# SOTB_LWC.net
KiCad netlist of a schematic drawn in EAGLE
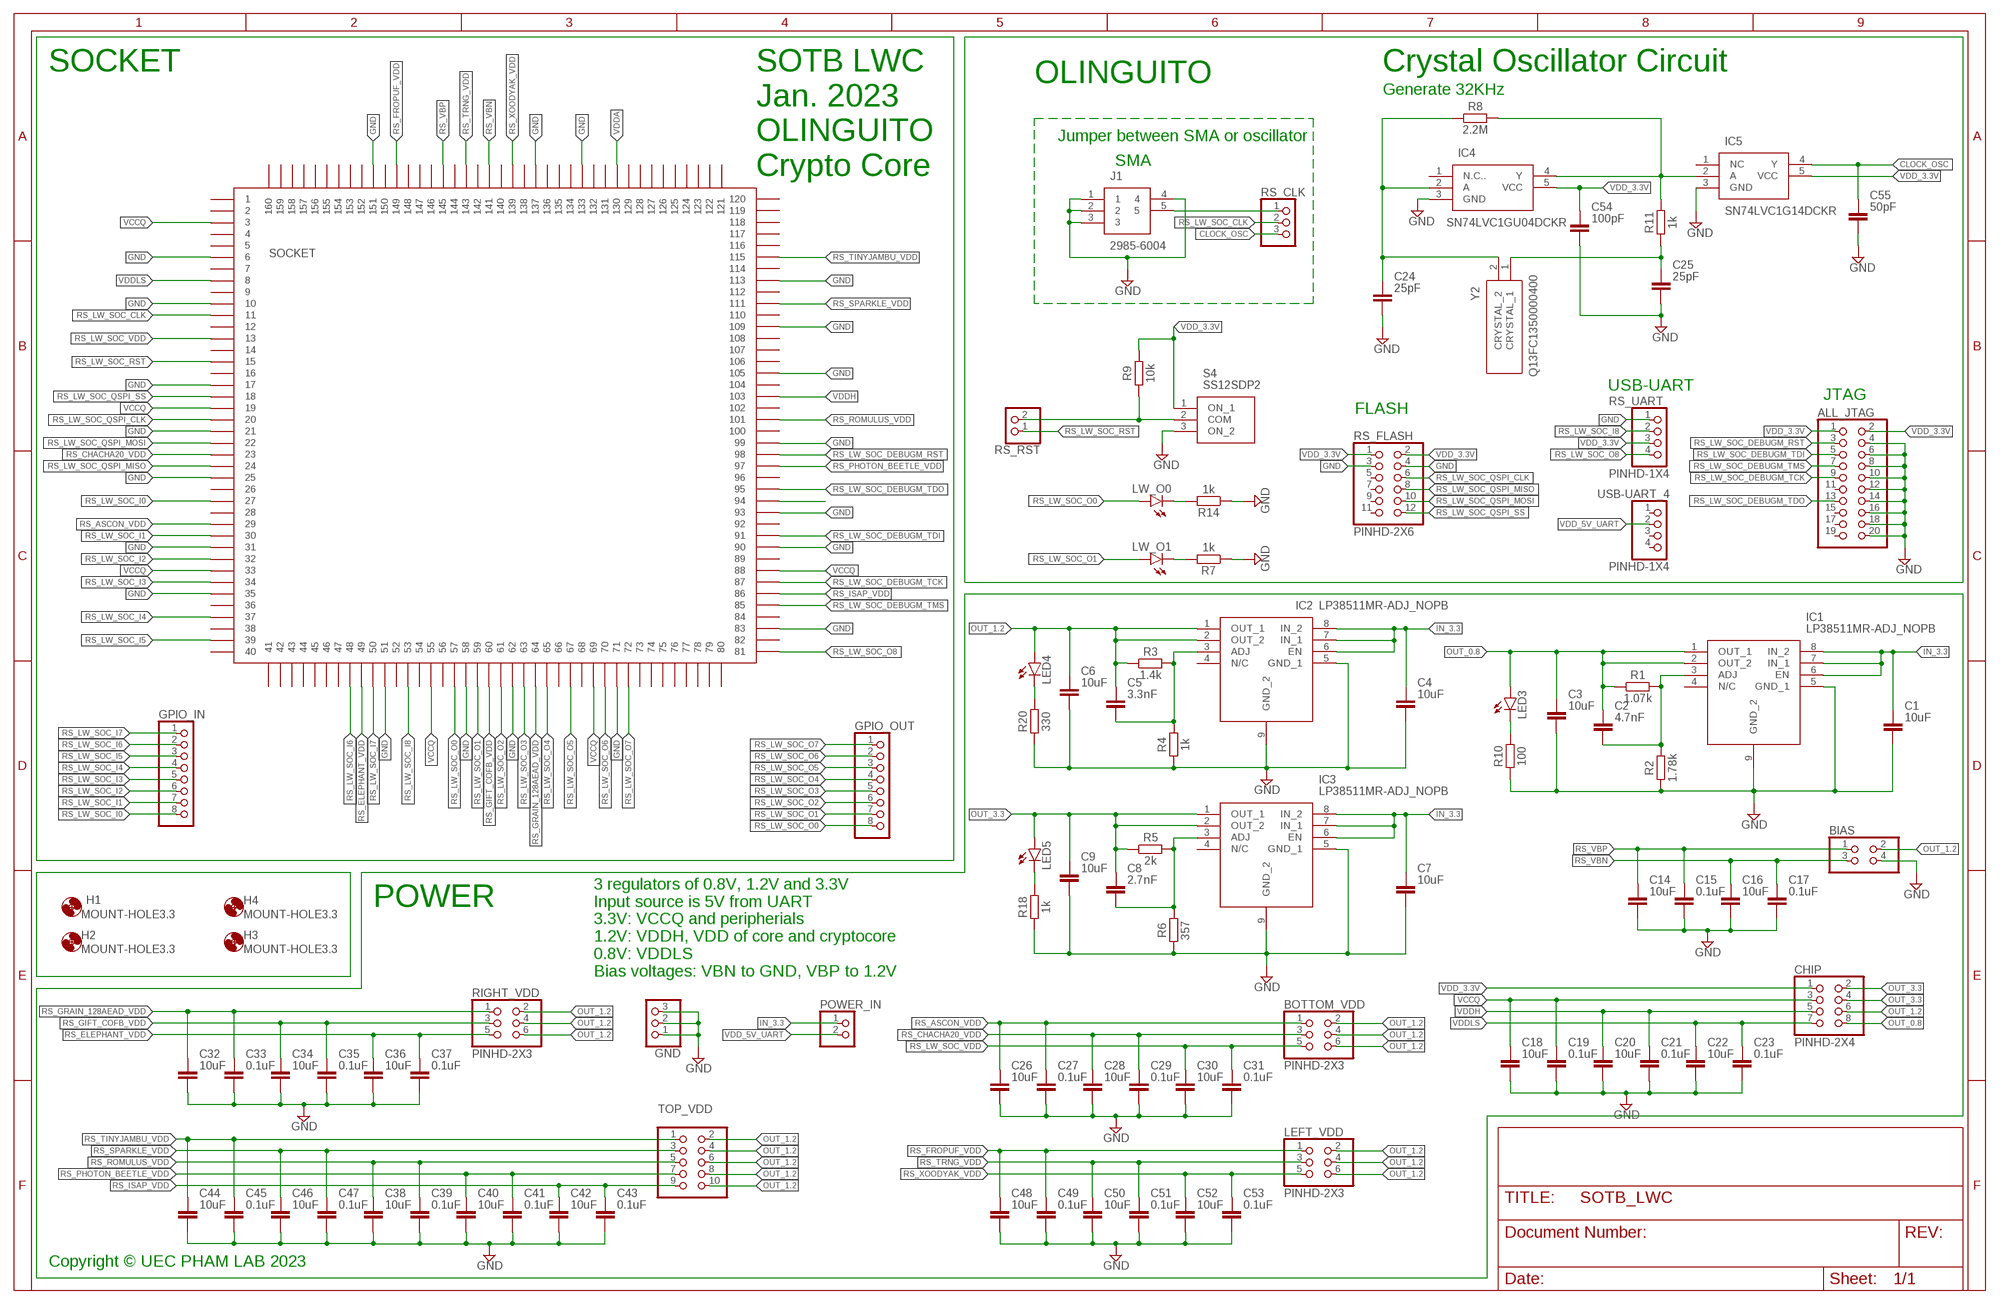
[diagram p0: schematic, sheet 1]

(export (version "E")
  (design (tool "Eeschema 10.0.6"))
  (components
    (comp (ref "ALL_JTAG")
      (value "PINHD-2X10")
      (footprint "eagle-import:2X10")
      (libsource (lib "eagle-import") (part "PINHD-2X10"))
    )
    (comp (ref "BIAS")
      (value "PINHD-2X2")
      (footprint "eagle-import:2X02")
      (libsource (lib "eagle-import") (part "PINHD-2X2"))
    )
    (comp (ref "BOTTOM_VDD")
      (value "PINHD-2X3")
      (footprint "eagle-import:2X03")
      (libsource (lib "eagle-import") (part "PINHD-2X3"))
    )
    (comp (ref "C1")
      (value "10uF")
      (footprint "eagle-import:CAPC3216X135")
      (libsource (lib "eagle-import") (part "CCHIP-1206(3216-METRIC)_"))
    )
    (comp (ref "C2")
      (value "4.7nF")
      (footprint "eagle-import:CAPC3216X135")
      (libsource (lib "eagle-import") (part "CCHIP-1206(3216-METRIC)_"))
    )
    (comp (ref "C3")
      (value "10uF")
      (footprint "eagle-import:CAPC3216X135")
      (libsource (lib "eagle-import") (part "CCHIP-1206(3216-METRIC)_"))
    )
    (comp (ref "C4")
      (value "10uF")
      (footprint "eagle-import:CAPC3216X135")
      (libsource (lib "eagle-import") (part "CCHIP-1206(3216-METRIC)_"))
    )
    (comp (ref "C5")
      (value "3.3nF")
      (footprint "eagle-import:CAPC3216X135")
      (libsource (lib "eagle-import") (part "CCHIP-1206(3216-METRIC)_"))
    )
    (comp (ref "C6")
      (value "10uF")
      (footprint "eagle-import:CAPC3216X135")
      (libsource (lib "eagle-import") (part "CCHIP-1206(3216-METRIC)_"))
    )
    (comp (ref "C7")
      (value "10uF")
      (footprint "eagle-import:CAPC3216X135")
      (libsource (lib "eagle-import") (part "CCHIP-1206(3216-METRIC)_"))
    )
    (comp (ref "C8")
      (value "2.7nF")
      (footprint "eagle-import:CAPC3216X135")
      (libsource (lib "eagle-import") (part "CCHIP-1206(3216-METRIC)_"))
    )
    (comp (ref "C9")
      (value "10uF")
      (footprint "eagle-import:CAPC3216X135")
      (libsource (lib "eagle-import") (part "CCHIP-1206(3216-METRIC)_"))
    )
    (comp (ref "C14")
      (value "10uF")
      (footprint "eagle-import:CAPC3216X135")
      (libsource (lib "eagle-import") (part "CCHIP-1206(3216-METRIC)_"))
    )
    (comp (ref "C15")
      (value "0.1uF")
      (footprint "eagle-import:CAPC3216X135")
      (libsource (lib "eagle-import") (part "CCHIP-1206(3216-METRIC)_"))
    )
    (comp (ref "C16")
      (value "10uF")
      (footprint "eagle-import:CAPC3216X135")
      (libsource (lib "eagle-import") (part "CCHIP-1206(3216-METRIC)_"))
    )
    (comp (ref "C17")
      (value "0.1uF")
      (footprint "eagle-import:CAPC3216X135")
      (libsource (lib "eagle-import") (part "CCHIP-1206(3216-METRIC)_"))
    )
    (comp (ref "C18")
      (value "10uF")
      (footprint "eagle-import:CAPC3216X135")
      (libsource (lib "eagle-import") (part "CCHIP-1206(3216-METRIC)_"))
    )
    (comp (ref "C19")
      (value "0.1uF")
      (footprint "eagle-import:CAPC3216X135")
      (libsource (lib "eagle-import") (part "CCHIP-1206(3216-METRIC)_"))
    )
    (comp (ref "C20")
      (value "10uF")
      (footprint "eagle-import:CAPC3216X135")
      (libsource (lib "eagle-import") (part "CCHIP-1206(3216-METRIC)_"))
    )
    (comp (ref "C21")
      (value "0.1uF")
      (footprint "eagle-import:CAPC3216X135")
      (libsource (lib "eagle-import") (part "CCHIP-1206(3216-METRIC)_"))
    )
    (comp (ref "C22")
      (value "10uF")
      (footprint "eagle-import:CAPC3216X135")
      (libsource (lib "eagle-import") (part "CCHIP-1206(3216-METRIC)_"))
    )
    (comp (ref "C23")
      (value "0.1uF")
      (footprint "eagle-import:CAPC3216X135")
      (libsource (lib "eagle-import") (part "CCHIP-1206(3216-METRIC)_"))
    )
    (comp (ref "C24")
      (value "25pF")
      (footprint "eagle-import:CAPC2012X110")
      (libsource (lib "eagle-import") (part "CCHIP-0805(2012-METRIC)_"))
    )
    (comp (ref "C25")
      (value "25pF")
      (footprint "eagle-import:CAPC2012X110")
      (libsource (lib "eagle-import") (part "CCHIP-0805(2012-METRIC)_"))
    )
    (comp (ref "C26")
      (value "10uF")
      (footprint "eagle-import:CAPC3216X135")
      (libsource (lib "eagle-import") (part "CCHIP-1206(3216-METRIC)_"))
    )
    (comp (ref "C27")
      (value "0.1uF")
      (footprint "eagle-import:CAPC3216X135")
      (libsource (lib "eagle-import") (part "CCHIP-1206(3216-METRIC)_"))
    )
    (comp (ref "C28")
      (value "10uF")
      (footprint "eagle-import:CAPC3216X135")
      (libsource (lib "eagle-import") (part "CCHIP-1206(3216-METRIC)_"))
    )
    (comp (ref "C29")
      (value "0.1uF")
      (footprint "eagle-import:CAPC3216X135")
      (libsource (lib "eagle-import") (part "CCHIP-1206(3216-METRIC)_"))
    )
    (comp (ref "C30")
      (value "10uF")
      (footprint "eagle-import:CAPC3216X135")
      (libsource (lib "eagle-import") (part "CCHIP-1206(3216-METRIC)_"))
    )
    (comp (ref "C31")
      (value "0.1uF")
      (footprint "eagle-import:CAPC3216X135")
      (libsource (lib "eagle-import") (part "CCHIP-1206(3216-METRIC)_"))
    )
    (comp (ref "C32")
      (value "10uF")
      (footprint "eagle-import:CAPC3216X135")
      (libsource (lib "eagle-import") (part "CCHIP-1206(3216-METRIC)_"))
    )
    (comp (ref "C33")
      (value "0.1uF")
      (footprint "eagle-import:CAPC3216X135")
      (libsource (lib "eagle-import") (part "CCHIP-1206(3216-METRIC)_"))
    )
    (comp (ref "C34")
      (value "10uF")
      (footprint "eagle-import:CAPC3216X135")
      (libsource (lib "eagle-import") (part "CCHIP-1206(3216-METRIC)_"))
    )
    (comp (ref "C35")
      (value "0.1uF")
      (footprint "eagle-import:CAPC3216X135")
      (libsource (lib "eagle-import") (part "CCHIP-1206(3216-METRIC)_"))
    )
    (comp (ref "C36")
      (value "10uF")
      (footprint "eagle-import:CAPC3216X135")
      (libsource (lib "eagle-import") (part "CCHIP-1206(3216-METRIC)_"))
    )
    (comp (ref "C37")
      (value "0.1uF")
      (footprint "eagle-import:CAPC3216X135")
      (libsource (lib "eagle-import") (part "CCHIP-1206(3216-METRIC)_"))
    )
    (comp (ref "C38")
      (value "10uF")
      (footprint "eagle-import:CAPC3216X135")
      (libsource (lib "eagle-import") (part "CCHIP-1206(3216-METRIC)_"))
    )
    (comp (ref "C39")
      (value "0.1uF")
      (footprint "eagle-import:CAPC3216X135")
      (libsource (lib "eagle-import") (part "CCHIP-1206(3216-METRIC)_"))
    )
    (comp (ref "C40")
      (value "10uF")
      (footprint "eagle-import:CAPC3216X135")
      (libsource (lib "eagle-import") (part "CCHIP-1206(3216-METRIC)_"))
    )
    (comp (ref "C41")
      (value "0.1uF")
      (footprint "eagle-import:CAPC3216X135")
      (libsource (lib "eagle-import") (part "CCHIP-1206(3216-METRIC)_"))
    )
    (comp (ref "C42")
      (value "10uF")
      (footprint "eagle-import:CAPC3216X135")
      (libsource (lib "eagle-import") (part "CCHIP-1206(3216-METRIC)_"))
    )
    (comp (ref "C43")
      (value "0.1uF")
      (footprint "eagle-import:CAPC3216X135")
      (libsource (lib "eagle-import") (part "CCHIP-1206(3216-METRIC)_"))
    )
    (comp (ref "C44")
      (value "10uF")
      (footprint "eagle-import:CAPC3216X135")
      (libsource (lib "eagle-import") (part "CCHIP-1206(3216-METRIC)_"))
    )
    (comp (ref "C45")
      (value "0.1uF")
      (footprint "eagle-import:CAPC3216X135")
      (libsource (lib "eagle-import") (part "CCHIP-1206(3216-METRIC)_"))
    )
    (comp (ref "C46")
      (value "10uF")
      (footprint "eagle-import:CAPC3216X135")
      (libsource (lib "eagle-import") (part "CCHIP-1206(3216-METRIC)_"))
    )
    (comp (ref "C47")
      (value "0.1uF")
      (footprint "eagle-import:CAPC3216X135")
      (libsource (lib "eagle-import") (part "CCHIP-1206(3216-METRIC)_"))
    )
    (comp (ref "C48")
      (value "10uF")
      (footprint "eagle-import:CAPC3216X135")
      (libsource (lib "eagle-import") (part "CCHIP-1206(3216-METRIC)_"))
    )
    (comp (ref "C49")
      (value "0.1uF")
      (footprint "eagle-import:CAPC3216X135")
      (libsource (lib "eagle-import") (part "CCHIP-1206(3216-METRIC)_"))
    )
    (comp (ref "C50")
      (value "10uF")
      (footprint "eagle-import:CAPC3216X135")
      (libsource (lib "eagle-import") (part "CCHIP-1206(3216-METRIC)_"))
    )
    (comp (ref "C51")
      (value "0.1uF")
      (footprint "eagle-import:CAPC3216X135")
      (libsource (lib "eagle-import") (part "CCHIP-1206(3216-METRIC)_"))
    )
    (comp (ref "C52")
      (value "10uF")
      (footprint "eagle-import:CAPC3216X135")
      (libsource (lib "eagle-import") (part "CCHIP-1206(3216-METRIC)_"))
    )
    (comp (ref "C53")
      (value "0.1uF")
      (footprint "eagle-import:CAPC3216X135")
      (libsource (lib "eagle-import") (part "CCHIP-1206(3216-METRIC)_"))
    )
    (comp (ref "C54")
      (value "100pF")
      (footprint "eagle-import:CAPC2012X110")
      (libsource (lib "eagle-import") (part "CCHIP-0805(2012-METRIC)_"))
    )
    (comp (ref "C55")
      (value "50pF")
      (footprint "eagle-import:CAPC2012X110")
      (libsource (lib "eagle-import") (part "CCHIP-0805(2012-METRIC)_"))
    )
    (comp (ref "CHIP")
      (value "PINHD-2X4")
      (footprint "eagle-import:2X04")
      (libsource (lib "eagle-import") (part "PINHD-2X4"))
    )
    (comp (ref "GND")
      (value "PINHD-1X3")
      (footprint "eagle-import:1X03")
      (libsource (lib "eagle-import") (part "PINHD-1X3"))
    )
    (comp (ref "GPIO_IN")
      (value "PINHD-1X8")
      (footprint "eagle-import:1X08")
      (libsource (lib "eagle-import") (part "PINHD-1X8"))
    )
    (comp (ref "GPIO_OUT")
      (value "PINHD-1X8")
      (footprint "eagle-import:1X08")
      (libsource (lib "eagle-import") (part "PINHD-1X8"))
    )
    (comp (ref "H1")
      (value "MOUNT-HOLE3.3")
      (footprint "eagle-import:3,3")
      (libsource (lib "eagle-import") (part "MOUNT-HOLE3.3"))
    )
    (comp (ref "H2")
      (value "MOUNT-HOLE3.3")
      (footprint "eagle-import:3,3")
      (libsource (lib "eagle-import") (part "MOUNT-HOLE3.3"))
    )
    (comp (ref "H3")
      (value "MOUNT-HOLE3.3")
      (footprint "eagle-import:3,3")
      (libsource (lib "eagle-import") (part "MOUNT-HOLE3.3"))
    )
    (comp (ref "H4")
      (value "MOUNT-HOLE3.3")
      (footprint "eagle-import:3,3")
      (libsource (lib "eagle-import") (part "MOUNT-HOLE3.3"))
    )
    (comp (ref "IC1")
      (value "LP38511MR-ADJ_NOPB")
      (footprint "eagle-import:SOIC127P600X170-9N")
      (fields
        (field (name "ARROW_PART_NUMBER") "LP38511MR-ADJ/NOPB")
        (field (name "MOUSER_PART_NUMBER") "926-38511MR-ADJ/NOPB")
      )
      (libsource (lib "eagle-import") (part "LP38511MR-ADJ_NOPB"))
    )
    (comp (ref "IC2")
      (value "LP38511MR-ADJ_NOPB")
      (footprint "eagle-import:SOIC127P600X170-9N")
      (fields
        (field (name "ARROW_PART_NUMBER") "LP38511MR-ADJ/NOPB")
        (field (name "MOUSER_PART_NUMBER") "926-38511MR-ADJ/NOPB")
      )
      (libsource (lib "eagle-import") (part "LP38511MR-ADJ_NOPB"))
    )
    (comp (ref "IC3")
      (value "LP38511MR-ADJ_NOPB")
      (footprint "eagle-import:SOIC127P600X170-9N")
      (fields
        (field (name "ARROW_PART_NUMBER") "LP38511MR-ADJ/NOPB")
        (field (name "MOUSER_PART_NUMBER") "926-38511MR-ADJ/NOPB")
      )
      (libsource (lib "eagle-import") (part "LP38511MR-ADJ_NOPB"))
    )
    (comp (ref "IC4")
      (value "SN74LVC1GU04DCKR")
      (footprint "eagle-import:SOT65P210X110-5N")
      (fields (field (name "MOUSER_PART_NUMBER") "595-SN74LVC1GU04DCKR"))
      (libsource (lib "eagle-import") (part "SN74LVC1GU04DCKR"))
    )
    (comp (ref "IC5")
      (value "SN74LVC1G14DCKR")
      (footprint "eagle-import:SOT65P210X110-5N")
      (fields (field (name "MOUSER_PART_NUMBER") "595-SN74LVC1G14DCKR"))
      (libsource (lib "eagle-import") (part "SN74LVC1G14DCKR"))
    )
    (comp (ref "J1")
      (value "2985-6004")
      (footprint "eagle-import:29856004")
      (fields (field (name "MOUSER_PART_NUMBER") "523-2985-6004"))
      (libsource (lib "eagle-import") (part "2985-6004"))
    )
    (comp (ref "LED3")
      (value "LEDCHIPLED_0805")
      (footprint "eagle-import:CHIPLED_0805")
      (libsource (lib "eagle-import") (part "LEDCHIPLED_0805"))
    )
    (comp (ref "LED4")
      (value "LEDCHIPLED_0805")
      (footprint "eagle-import:CHIPLED_0805")
      (libsource (lib "eagle-import") (part "LEDCHIPLED_0805"))
    )
    (comp (ref "LED5")
      (value "LEDCHIPLED_0805")
      (footprint "eagle-import:CHIPLED_0805")
      (libsource (lib "eagle-import") (part "LEDCHIPLED_0805"))
    )
    (comp (ref "LEFT_VDD")
      (value "PINHD-2X3")
      (footprint "eagle-import:2X03")
      (libsource (lib "eagle-import") (part "PINHD-2X3"))
    )
    (comp (ref "LW_O0")
      (value "LEDCHIPLED_0805")
      (footprint "eagle-import:CHIPLED_0805")
      (libsource (lib "eagle-import") (part "LEDCHIPLED_0805"))
    )
    (comp (ref "LW_O1")
      (value "LEDCHIPLED_0805")
      (footprint "eagle-import:CHIPLED_0805")
      (libsource (lib "eagle-import") (part "LEDCHIPLED_0805"))
    )
    (comp (ref "POWER_IN")
      (value "PINHD-1X2")
      (footprint "eagle-import:1X02")
      (libsource (lib "eagle-import") (part "PINHD-1X2"))
    )
    (comp (ref "R1")
      (value "1.07k")
      (footprint "eagle-import:RESC3216X70")
      (libsource (lib "eagle-import") (part "RCHIP-1206(3216-METRIC)_"))
    )
    (comp (ref "R2")
      (value "1.78k")
      (footprint "eagle-import:RESC3216X70")
      (libsource (lib "eagle-import") (part "RCHIP-1206(3216-METRIC)_"))
    )
    (comp (ref "R3")
      (value "1.4k")
      (footprint "eagle-import:RESC3216X70")
      (libsource (lib "eagle-import") (part "RCHIP-1206(3216-METRIC)_"))
    )
    (comp (ref "R4")
      (value "1k")
      (footprint "eagle-import:RESC3216X70")
      (libsource (lib "eagle-import") (part "RCHIP-1206(3216-METRIC)_"))
    )
    (comp (ref "R5")
      (value "2k")
      (footprint "eagle-import:RESC3216X70")
      (libsource (lib "eagle-import") (part "RCHIP-1206(3216-METRIC)_"))
    )
    (comp (ref "R6")
      (value "357")
      (footprint "eagle-import:RESC3216X70")
      (libsource (lib "eagle-import") (part "RCHIP-1206(3216-METRIC)_"))
    )
    (comp (ref "R7")
      (value "1k")
      (footprint "eagle-import:RESC3216X70")
      (libsource (lib "eagle-import") (part "RCHIP-1206(3216-METRIC)_"))
    )
    (comp (ref "R8")
      (value "2.2M")
      (footprint "eagle-import:RESC3216X70")
      (libsource (lib "eagle-import") (part "RCHIP-1206(3216-METRIC)_"))
    )
    (comp (ref "R9")
      (value "10k")
      (footprint "eagle-import:RESC3216X70")
      (libsource (lib "eagle-import") (part "RCHIP-1206(3216-METRIC)_"))
    )
    (comp (ref "R10")
      (value "100")
      (footprint "eagle-import:RESC3216X70")
      (libsource (lib "eagle-import") (part "RCHIP-1206(3216-METRIC)_"))
    )
    (comp (ref "R11")
      (value "1k")
      (footprint "eagle-import:RESC3216X70")
      (libsource (lib "eagle-import") (part "RCHIP-1206(3216-METRIC)_"))
    )
    (comp (ref "R14")
      (value "1k")
      (footprint "eagle-import:RESC3216X70")
      (libsource (lib "eagle-import") (part "RCHIP-1206(3216-METRIC)_"))
    )
    (comp (ref "R18")
      (value "1k")
      (footprint "eagle-import:RESC3216X70")
      (libsource (lib "eagle-import") (part "RCHIP-1206(3216-METRIC)_"))
    )
    (comp (ref "R20")
      (value "330")
      (footprint "eagle-import:RESC3216X70")
      (libsource (lib "eagle-import") (part "RCHIP-1206(3216-METRIC)_"))
    )
    (comp (ref "RIGHT_VDD")
      (value "PINHD-2X3")
      (footprint "eagle-import:2X03")
      (libsource (lib "eagle-import") (part "PINHD-2X3"))
    )
    (comp (ref "RS_CLK")
      (value "PINHD-1X3")
      (footprint "eagle-import:1X03")
      (libsource (lib "eagle-import") (part "PINHD-1X3"))
    )
    (comp (ref "RS_FLASH")
      (value "PINHD-2X6")
      (footprint "eagle-import:2X06")
      (libsource (lib "eagle-import") (part "PINHD-2X6"))
    )
    (comp (ref "RS_RST")
      (value "PINHD-1X2")
      (footprint "eagle-import:1X02")
      (libsource (lib "eagle-import") (part "PINHD-1X2"))
    )
    (comp (ref "RS_UART")
      (value "PINHD-1X4")
      (footprint "eagle-import:1X04")
      (libsource (lib "eagle-import") (part "PINHD-1X4"))
    )
    (comp (ref "S4")
      (value "SS12SDP2")
      (footprint "eagle-import:SS12SDP2")
      (fields (field (name "MOUSER_PART_NUMBER") "633-SS12SDP2"))
      (libsource (lib "eagle-import") (part "SS12SDP2"))
    )
    (comp (ref "SOCKET")
      (value "QFP28-160PIN")
      (footprint "eagle-import:QFP28-160PIN")
      (libsource (lib "eagle-import") (part "QFP28-160PIN"))
    )
    (comp (ref "TOP_VDD")
      (value "PINHD-2X5")
      (footprint "eagle-import:2X05")
      (libsource (lib "eagle-import") (part "PINHD-2X5"))
    )
    (comp (ref "USB-UART_4")
      (value "PINHD-1X4")
      (footprint "eagle-import:1X04")
      (libsource (lib "eagle-import") (part "PINHD-1X4"))
    )
    (comp (ref "Y2")
      (value "Q13FC1350000400")
      (footprint "eagle-import:Q13FC1350000400")
      (libsource (lib "eagle-import") (part "Q13FC1350000400"))
    )
  )
  (nets
    (net (code "1") (name "CLOCK_OSC") (class "Default")
      (node (ref "C55") (pin "1") (pinfunction "1_1") (pintype "passive"))
      (node (ref "IC5") (pin "4") (pinfunction "Y_4") (pintype "bidirectional"))
      (node (ref "RS_CLK") (pin "3") (pinfunction "3_3") (pintype "passive"))
    )
    (net (code "2") (name "GND") (class "Default")
      (node (ref "ALL_JTAG") (pin "10") (pinfunction "10_10") (pintype "passive"))
      (node (ref "ALL_JTAG") (pin "12") (pinfunction "12_12") (pintype "passive"))
      (node (ref "ALL_JTAG") (pin "14") (pinfunction "14_14") (pintype "passive"))
      (node (ref "ALL_JTAG") (pin "16") (pinfunction "16_16") (pintype "passive"))
      (node (ref "ALL_JTAG") (pin "18") (pinfunction "18_18") (pintype "passive"))
      (node (ref "ALL_JTAG") (pin "20") (pinfunction "20_20") (pintype "passive"))
      (node (ref "ALL_JTAG") (pin "4") (pinfunction "4_4") (pintype "passive"))
      (node (ref "ALL_JTAG") (pin "6") (pinfunction "6_6") (pintype "passive"))
      (node (ref "ALL_JTAG") (pin "8") (pinfunction "8_8") (pintype "passive"))
      (node (ref "BIAS") (pin "4") (pinfunction "4_4") (pintype "passive"))
      (node (ref "C1") (pin "2") (pinfunction "2_2") (pintype "passive"))
      (node (ref "C14") (pin "2") (pinfunction "2_2") (pintype "passive"))
      (node (ref "C15") (pin "2") (pinfunction "2_2") (pintype "passive"))
      (node (ref "C16") (pin "2") (pinfunction "2_2") (pintype "passive"))
      (node (ref "C17") (pin "2") (pinfunction "2_2") (pintype "passive"))
      (node (ref "C18") (pin "2") (pinfunction "2_2") (pintype "passive"))
      (node (ref "C19") (pin "2") (pinfunction "2_2") (pintype "passive"))
      (node (ref "C20") (pin "2") (pinfunction "2_2") (pintype "passive"))
      (node (ref "C21") (pin "2") (pinfunction "2_2") (pintype "passive"))
      (node (ref "C22") (pin "2") (pinfunction "2_2") (pintype "passive"))
      (node (ref "C23") (pin "2") (pinfunction "2_2") (pintype "passive"))
      (node (ref "C24") (pin "2") (pinfunction "2_2") (pintype "passive"))
      (node (ref "C25") (pin "2") (pinfunction "2_2") (pintype "passive"))
      (node (ref "C26") (pin "2") (pinfunction "2_2") (pintype "passive"))
      (node (ref "C27") (pin "2") (pinfunction "2_2") (pintype "passive"))
      (node (ref "C28") (pin "2") (pinfunction "2_2") (pintype "passive"))
      (node (ref "C29") (pin "2") (pinfunction "2_2") (pintype "passive"))
      (node (ref "C3") (pin "2") (pinfunction "2_2") (pintype "passive"))
      (node (ref "C30") (pin "2") (pinfunction "2_2") (pintype "passive"))
      (node (ref "C31") (pin "2") (pinfunction "2_2") (pintype "passive"))
      (node (ref "C32") (pin "2") (pinfunction "2_2") (pintype "passive"))
      (node (ref "C33") (pin "2") (pinfunction "2_2") (pintype "passive"))
      (node (ref "C34") (pin "2") (pinfunction "2_2") (pintype "passive"))
      (node (ref "C35") (pin "2") (pinfunction "2_2") (pintype "passive"))
      (node (ref "C36") (pin "2") (pinfunction "2_2") (pintype "passive"))
      (node (ref "C37") (pin "2") (pinfunction "2_2") (pintype "passive"))
      (node (ref "C38") (pin "2") (pinfunction "2_2") (pintype "passive"))
      (node (ref "C39") (pin "2") (pinfunction "2_2") (pintype "passive"))
      (node (ref "C4") (pin "2") (pinfunction "2_2") (pintype "passive"))
      (node (ref "C40") (pin "2") (pinfunction "2_2") (pintype "passive"))
      (node (ref "C41") (pin "2") (pinfunction "2_2") (pintype "passive"))
      (node (ref "C42") (pin "2") (pinfunction "2_2") (pintype "passive"))
      (node (ref "C43") (pin "2") (pinfunction "2_2") (pintype "passive"))
      (node (ref "C44") (pin "2") (pinfunction "2_2") (pintype "passive"))
      (node (ref "C45") (pin "2") (pinfunction "2_2") (pintype "passive"))
      (node (ref "C46") (pin "2") (pinfunction "2_2") (pintype "passive"))
      (node (ref "C47") (pin "2") (pinfunction "2_2") (pintype "passive"))
      (node (ref "C48") (pin "2") (pinfunction "2_2") (pintype "passive"))
      (node (ref "C49") (pin "2") (pinfunction "2_2") (pintype "passive"))
      (node (ref "C50") (pin "2") (pinfunction "2_2") (pintype "passive"))
      (node (ref "C51") (pin "2") (pinfunction "2_2") (pintype "passive"))
      (node (ref "C52") (pin "2") (pinfunction "2_2") (pintype "passive"))
      (node (ref "C53") (pin "2") (pinfunction "2_2") (pintype "passive"))
      (node (ref "C54") (pin "2") (pinfunction "2_2") (pintype "passive"))
      (node (ref "C55") (pin "2") (pinfunction "2_2") (pintype "passive"))
      (node (ref "C6") (pin "2") (pinfunction "2_2") (pintype "passive"))
      (node (ref "C7") (pin "2") (pinfunction "2_2") (pintype "passive"))
      (node (ref "C9") (pin "2") (pinfunction "2_2") (pintype "passive"))
      (node (ref "GND") (pin "1") (pinfunction "1_1") (pintype "passive"))
      (node (ref "GND") (pin "2") (pinfunction "2_2") (pintype "passive"))
      (node (ref "GND") (pin "3") (pinfunction "3_3") (pintype "passive"))
      (node (ref "IC1") (pin "5") (pinfunction "GND_1_5") (pintype "bidirectional"))
      (node (ref "IC1") (pin "9") (pinfunction "GND_2_9") (pintype "bidirectional"))
      (node (ref "IC2") (pin "5") (pinfunction "GND_1_5") (pintype "bidirectional"))
      (node (ref "IC2") (pin "9") (pinfunction "GND_2_9") (pintype "bidirectional"))
      (node (ref "IC3") (pin "5") (pinfunction "GND_1_5") (pintype "bidirectional"))
      (node (ref "IC3") (pin "9") (pinfunction "GND_2_9") (pintype "bidirectional"))
      (node (ref "IC4") (pin "3") (pinfunction "GND_3") (pintype "bidirectional"))
      (node (ref "IC5") (pin "3") (pinfunction "GND_3") (pintype "power_in"))
      (node (ref "J1") (pin "1") (pinfunction "1_1") (pintype "bidirectional"))
      (node (ref "J1") (pin "2") (pinfunction "2_2") (pintype "bidirectional"))
      (node (ref "J1") (pin "3") (pinfunction "3_3") (pintype "bidirectional"))
      (node (ref "J1") (pin "4") (pinfunction "4_4") (pintype "bidirectional"))
      (node (ref "R10") (pin "1") (pinfunction "1_1") (pintype "passive"))
      (node (ref "R14") (pin "1") (pinfunction "1_1") (pintype "passive"))
      (node (ref "R18") (pin "1") (pinfunction "1_1") (pintype "passive"))
      (node (ref "R2") (pin "1") (pinfunction "1_1") (pintype "passive"))
      (node (ref "R20") (pin "1") (pinfunction "1_1") (pintype "passive"))
      (node (ref "R4") (pin "1") (pinfunction "1_1") (pintype "passive"))
      (node (ref "R6") (pin "1") (pinfunction "1_1") (pintype "passive"))
      (node (ref "R7") (pin "1") (pinfunction "1_1") (pintype "passive"))
      (node (ref "RS_FLASH") (pin "3") (pinfunction "3_3") (pintype "passive"))
      (node (ref "RS_FLASH") (pin "4") (pinfunction "4_4") (pintype "passive"))
      (node (ref "RS_UART") (pin "1") (pinfunction "1_1") (pintype "passive"))
      (node (ref "S4") (pin "3") (pinfunction "ON_2_3") (pintype "bidirectional"))
      (node (ref "SOCKET") (pin "P$10") (pinfunction "10_P$10") (pintype "bidirectional"))
      (node (ref "SOCKET") (pin "P$105") (pinfunction "105_P$105") (pintype "bidirectional"))
      (node (ref "SOCKET") (pin "P$109") (pinfunction "109_P$109") (pintype "bidirectional"))
      (node (ref "SOCKET") (pin "P$113") (pinfunction "113_P$113") (pintype "bidirectional"))
      (node (ref "SOCKET") (pin "P$133") (pinfunction "133_P$133") (pintype "bidirectional"))
      (node (ref "SOCKET") (pin "P$137") (pinfunction "137_P$137") (pintype "bidirectional"))
      (node (ref "SOCKET") (pin "P$151") (pinfunction "151_P$151") (pintype "bidirectional"))
      (node (ref "SOCKET") (pin "P$17") (pinfunction "17_P$17") (pintype "bidirectional"))
      (node (ref "SOCKET") (pin "P$21") (pinfunction "21_P$21") (pintype "bidirectional"))
      (node (ref "SOCKET") (pin "P$25") (pinfunction "25_P$25") (pintype "bidirectional"))
      (node (ref "SOCKET") (pin "P$31") (pinfunction "31_P$31") (pintype "bidirectional"))
      (node (ref "SOCKET") (pin "P$35") (pinfunction "35_P$35") (pintype "bidirectional"))
      (node (ref "SOCKET") (pin "P$51") (pinfunction "51_P$51") (pintype "bidirectional"))
      (node (ref "SOCKET") (pin "P$58") (pinfunction "58_P$58") (pintype "bidirectional"))
      (node (ref "SOCKET") (pin "P$6") (pinfunction "6_P$6") (pintype "bidirectional"))
      (node (ref "SOCKET") (pin "P$62") (pinfunction "62_P$62") (pintype "bidirectional"))
      (node (ref "SOCKET") (pin "P$71") (pinfunction "71_P$71") (pintype "bidirectional"))
      (node (ref "SOCKET") (pin "P$83") (pinfunction "83_P$83") (pintype "bidirectional"))
      (node (ref "SOCKET") (pin "P$90") (pinfunction "90_P$90") (pintype "bidirectional"))
      (node (ref "SOCKET") (pin "P$93") (pinfunction "93_P$93") (pintype "bidirectional"))
      (node (ref "SOCKET") (pin "P$99") (pinfunction "99_P$99") (pintype "bidirectional"))
    )
    (net (code "3") (name "IN_3.3") (class "Default")
      (node (ref "C1") (pin "1") (pinfunction "1_1") (pintype "passive"))
      (node (ref "C4") (pin "1") (pinfunction "1_1") (pintype "passive"))
      (node (ref "C7") (pin "1") (pinfunction "1_1") (pintype "passive"))
      (node (ref "IC1") (pin "6") (pinfunction "EN_6") (pintype "bidirectional"))
      (node (ref "IC1") (pin "7") (pinfunction "IN_1_7") (pintype "bidirectional"))
      (node (ref "IC1") (pin "8") (pinfunction "IN_2_8") (pintype "bidirectional"))
      (node (ref "IC2") (pin "6") (pinfunction "EN_6") (pintype "bidirectional"))
      (node (ref "IC2") (pin "7") (pinfunction "IN_1_7") (pintype "bidirectional"))
      (node (ref "IC2") (pin "8") (pinfunction "IN_2_8") (pintype "bidirectional"))
      (node (ref "IC3") (pin "6") (pinfunction "EN_6") (pintype "bidirectional"))
      (node (ref "IC3") (pin "7") (pinfunction "IN_1_7") (pintype "bidirectional"))
      (node (ref "IC3") (pin "8") (pinfunction "IN_2_8") (pintype "bidirectional"))
      (node (ref "POWER_IN") (pin "1") (pinfunction "1_1") (pintype "passive"))
    )
    (net (code "4") (name "Net-(IC1-ADJ)") (class "Default")
      (node (ref "C2") (pin "2") (pinfunction "2_2") (pintype "passive"))
      (node (ref "IC1") (pin "3") (pinfunction "ADJ_3") (pintype "bidirectional"))
      (node (ref "R1") (pin "2") (pinfunction "2_2") (pintype "passive"))
      (node (ref "R2") (pin "2") (pinfunction "2_2") (pintype "passive"))
    )
    (net (code "5") (name "Net-(IC2-ADJ)") (class "Default")
      (node (ref "C5") (pin "2") (pinfunction "2_2") (pintype "passive"))
      (node (ref "IC2") (pin "3") (pinfunction "ADJ_3") (pintype "bidirectional"))
      (node (ref "R3") (pin "2") (pinfunction "2_2") (pintype "passive"))
      (node (ref "R4") (pin "2") (pinfunction "2_2") (pintype "passive"))
    )
    (net (code "6") (name "Net-(IC3-ADJ)") (class "Default")
      (node (ref "C8") (pin "2") (pinfunction "2_2") (pintype "passive"))
      (node (ref "IC3") (pin "3") (pinfunction "ADJ_3") (pintype "bidirectional"))
      (node (ref "R5") (pin "2") (pinfunction "2_2") (pintype "passive"))
      (node (ref "R6") (pin "2") (pinfunction "2_2") (pintype "passive"))
    )
    (net (code "7") (name "Net-(IC4-A)") (class "Default")
      (node (ref "C24") (pin "1") (pinfunction "1_1") (pintype "passive"))
      (node (ref "IC4") (pin "2") (pinfunction "A_2") (pintype "bidirectional"))
      (node (ref "R8") (pin "1") (pinfunction "1_1") (pintype "passive"))
      (node (ref "Y2") (pin "2") (pinfunction "CRYSTAL_2_2") (pintype "bidirectional"))
    )
    (net (code "8") (name "Net-(IC4-Y)") (class "Default")
      (node (ref "IC4") (pin "4") (pinfunction "Y_4") (pintype "bidirectional"))
      (node (ref "IC5") (pin "2") (pinfunction "A_2") (pintype "bidirectional"))
      (node (ref "R11") (pin "2") (pinfunction "2_2") (pintype "passive"))
      (node (ref "R8") (pin "2") (pinfunction "2_2") (pintype "passive"))
    )
    (net (code "9") (name "Net-(J1-Pad5)") (class "Default")
      (node (ref "J1") (pin "5") (pinfunction "5_5") (pintype "bidirectional"))
      (node (ref "RS_CLK") (pin "1") (pinfunction "1_1") (pintype "passive"))
    )
    (net (code "10") (name "Net-(LED3-PadC)") (class "Default")
      (node (ref "LED3") (pin "C") (pinfunction "C_C") (pintype "passive"))
      (node (ref "R10") (pin "2") (pinfunction "2_2") (pintype "passive"))
    )
    (net (code "11") (name "Net-(LED4-PadC)") (class "Default")
      (node (ref "LED4") (pin "C") (pinfunction "C_C") (pintype "passive"))
      (node (ref "R20") (pin "2") (pinfunction "2_2") (pintype "passive"))
    )
    (net (code "12") (name "Net-(LED5-PadC)") (class "Default")
      (node (ref "LED5") (pin "C") (pinfunction "C_C") (pintype "passive"))
      (node (ref "R18") (pin "2") (pinfunction "2_2") (pintype "passive"))
    )
    (net (code "13") (name "Net-(LW_O0-PadC)") (class "Default")
      (node (ref "LW_O0") (pin "C") (pinfunction "C_C") (pintype "passive"))
      (node (ref "R14") (pin "2") (pinfunction "2_2") (pintype "passive"))
    )
    (net (code "14") (name "Net-(LW_O1-PadC)") (class "Default")
      (node (ref "LW_O1") (pin "C") (pinfunction "C_C") (pintype "passive"))
      (node (ref "R7") (pin "2") (pinfunction "2_2") (pintype "passive"))
    )
    (net (code "15") (name "Net-(S4-COM)") (class "Default")
      (node (ref "R9") (pin "1") (pinfunction "1_1") (pintype "passive"))
      (node (ref "RS_RST") (pin "2") (pinfunction "2_2") (pintype "passive"))
      (node (ref "S4") (pin "2") (pinfunction "COM_2") (pintype "bidirectional"))
    )
    (net (code "16") (name "Net-(Y2-CRYSTAL_1)") (class "Default")
      (node (ref "C25") (pin "1") (pinfunction "1_1") (pintype "passive"))
      (node (ref "R11") (pin "1") (pinfunction "1_1") (pintype "passive"))
      (node (ref "Y2") (pin "1") (pinfunction "CRYSTAL_1_1") (pintype "bidirectional"))
    )
    (net (code "17") (name "OUT_0.8") (class "Default")
      (node (ref "C2") (pin "1") (pinfunction "1_1") (pintype "passive"))
      (node (ref "C3") (pin "1") (pinfunction "1_1") (pintype "passive"))
      (node (ref "CHIP") (pin "8") (pinfunction "8_8") (pintype "passive"))
      (node (ref "IC1") (pin "1") (pinfunction "OUT_1_1") (pintype "bidirectional"))
      (node (ref "IC1") (pin "2") (pinfunction "OUT_2_2") (pintype "bidirectional"))
      (node (ref "LED3") (pin "A") (pinfunction "A_A") (pintype "passive"))
      (node (ref "R1") (pin "1") (pinfunction "1_1") (pintype "passive"))
    )
    (net (code "18") (name "OUT_1.2") (class "Default")
      (node (ref "BIAS") (pin "2") (pinfunction "2_2") (pintype "passive"))
      (node (ref "BOTTOM_VDD") (pin "2") (pinfunction "2_2") (pintype "passive"))
      (node (ref "BOTTOM_VDD") (pin "4") (pinfunction "4_4") (pintype "passive"))
      (node (ref "BOTTOM_VDD") (pin "6") (pinfunction "6_6") (pintype "passive"))
      (node (ref "C5") (pin "1") (pinfunction "1_1") (pintype "passive"))
      (node (ref "C6") (pin "1") (pinfunction "1_1") (pintype "passive"))
      (node (ref "CHIP") (pin "6") (pinfunction "6_6") (pintype "passive"))
      (node (ref "IC2") (pin "1") (pinfunction "OUT_1_1") (pintype "bidirectional"))
      (node (ref "IC2") (pin "2") (pinfunction "OUT_2_2") (pintype "bidirectional"))
      (node (ref "LED4") (pin "A") (pinfunction "A_A") (pintype "passive"))
      (node (ref "LEFT_VDD") (pin "2") (pinfunction "2_2") (pintype "passive"))
      (node (ref "LEFT_VDD") (pin "4") (pinfunction "4_4") (pintype "passive"))
      (node (ref "LEFT_VDD") (pin "6") (pinfunction "6_6") (pintype "passive"))
      (node (ref "R3") (pin "1") (pinfunction "1_1") (pintype "passive"))
      (node (ref "RIGHT_VDD") (pin "2") (pinfunction "2_2") (pintype "passive"))
      (node (ref "RIGHT_VDD") (pin "4") (pinfunction "4_4") (pintype "passive"))
      (node (ref "RIGHT_VDD") (pin "6") (pinfunction "6_6") (pintype "passive"))
      (node (ref "TOP_VDD") (pin "10") (pinfunction "10_10") (pintype "passive"))
      (node (ref "TOP_VDD") (pin "2") (pinfunction "2_2") (pintype "passive"))
      (node (ref "TOP_VDD") (pin "4") (pinfunction "4_4") (pintype "passive"))
      (node (ref "TOP_VDD") (pin "6") (pinfunction "6_6") (pintype "passive"))
      (node (ref "TOP_VDD") (pin "8") (pinfunction "8_8") (pintype "passive"))
    )
    (net (code "19") (name "OUT_3.3") (class "Default")
      (node (ref "C8") (pin "1") (pinfunction "1_1") (pintype "passive"))
      (node (ref "C9") (pin "1") (pinfunction "1_1") (pintype "passive"))
      (node (ref "CHIP") (pin "2") (pinfunction "2_2") (pintype "passive"))
      (node (ref "CHIP") (pin "4") (pinfunction "4_4") (pintype "passive"))
      (node (ref "IC3") (pin "1") (pinfunction "OUT_1_1") (pintype "bidirectional"))
      (node (ref "IC3") (pin "2") (pinfunction "OUT_2_2") (pintype "bidirectional"))
      (node (ref "LED5") (pin "A") (pinfunction "A_A") (pintype "passive"))
      (node (ref "R5") (pin "1") (pinfunction "1_1") (pintype "passive"))
    )
    (net (code "20") (name "RS_ASCON_VDD") (class "Default")
      (node (ref "BOTTOM_VDD") (pin "1") (pinfunction "1_1") (pintype "passive"))
      (node (ref "C26") (pin "1") (pinfunction "1_1") (pintype "passive"))
      (node (ref "C27") (pin "1") (pinfunction "1_1") (pintype "passive"))
      (node (ref "SOCKET") (pin "P$29") (pinfunction "29_P$29") (pintype "bidirectional"))
    )
    (net (code "21") (name "RS_CHACHA20_VDD") (class "Default")
      (node (ref "BOTTOM_VDD") (pin "3") (pinfunction "3_3") (pintype "passive"))
      (node (ref "C28") (pin "1") (pinfunction "1_1") (pintype "passive"))
      (node (ref "C29") (pin "1") (pinfunction "1_1") (pintype "passive"))
      (node (ref "SOCKET") (pin "P$23") (pinfunction "23_P$23") (pintype "bidirectional"))
    )
    (net (code "22") (name "RS_ELEPHANT_VDD") (class "Default")
      (node (ref "C36") (pin "1") (pinfunction "1_1") (pintype "passive"))
      (node (ref "C37") (pin "1") (pinfunction "1_1") (pintype "passive"))
      (node (ref "RIGHT_VDD") (pin "5") (pinfunction "5_5") (pintype "passive"))
      (node (ref "SOCKET") (pin "P$49") (pinfunction "49_P$49") (pintype "bidirectional"))
    )
    (net (code "23") (name "RS_FROPUF_VDD") (class "Default")
      (node (ref "C48") (pin "1") (pinfunction "1_1") (pintype "passive"))
      (node (ref "C49") (pin "1") (pinfunction "1_1") (pintype "passive"))
      (node (ref "LEFT_VDD") (pin "1") (pinfunction "1_1") (pintype "passive"))
      (node (ref "SOCKET") (pin "P$149") (pinfunction "149_P$149") (pintype "bidirectional"))
    )
    (net (code "24") (name "RS_GIFT_COFB_VDD") (class "Default")
      (node (ref "C34") (pin "1") (pinfunction "1_1") (pintype "passive"))
      (node (ref "C35") (pin "1") (pinfunction "1_1") (pintype "passive"))
      (node (ref "RIGHT_VDD") (pin "3") (pinfunction "3_3") (pintype "passive"))
      (node (ref "SOCKET") (pin "P$60") (pinfunction "60_P$60") (pintype "bidirectional"))
    )
    (net (code "25") (name "RS_GRAIN_128AEAD_VDD") (class "Default")
      (node (ref "C32") (pin "1") (pinfunction "1_1") (pintype "passive"))
      (node (ref "C33") (pin "1") (pinfunction "1_1") (pintype "passive"))
      (node (ref "RIGHT_VDD") (pin "1") (pinfunction "1_1") (pintype "passive"))
      (node (ref "SOCKET") (pin "P$64") (pinfunction "64_P$64") (pintype "bidirectional"))
    )
    (net (code "26") (name "RS_ISAP_VDD") (class "Default")
      (node (ref "C42") (pin "1") (pinfunction "1_1") (pintype "passive"))
      (node (ref "C43") (pin "1") (pinfunction "1_1") (pintype "passive"))
      (node (ref "SOCKET") (pin "P$86") (pinfunction "86_P$86") (pintype "bidirectional"))
      (node (ref "TOP_VDD") (pin "9") (pinfunction "9_9") (pintype "passive"))
    )
    (net (code "27") (name "RS_LW_SOC_CLK") (class "Default")
      (node (ref "RS_CLK") (pin "2") (pinfunction "2_2") (pintype "passive"))
      (node (ref "SOCKET") (pin "P$11") (pinfunction "11_P$11") (pintype "bidirectional"))
    )
    (net (code "28") (name "RS_LW_SOC_DEBUGM_RST") (class "Default")
      (node (ref "ALL_JTAG") (pin "3") (pinfunction "3_3") (pintype "passive"))
      (node (ref "SOCKET") (pin "P$98") (pinfunction "98_P$98") (pintype "bidirectional"))
    )
    (net (code "29") (name "RS_LW_SOC_DEBUGM_TCK") (class "Default")
      (node (ref "ALL_JTAG") (pin "9") (pinfunction "9_9") (pintype "passive"))
      (node (ref "SOCKET") (pin "P$87") (pinfunction "87_P$87") (pintype "bidirectional"))
    )
    (net (code "30") (name "RS_LW_SOC_DEBUGM_TDI") (class "Default")
      (node (ref "ALL_JTAG") (pin "5") (pinfunction "5_5") (pintype "passive"))
      (node (ref "SOCKET") (pin "P$91") (pinfunction "91_P$91") (pintype "bidirectional"))
    )
    (net (code "31") (name "RS_LW_SOC_DEBUGM_TDO") (class "Default")
      (node (ref "ALL_JTAG") (pin "13") (pinfunction "13_13") (pintype "passive"))
      (node (ref "SOCKET") (pin "P$95") (pinfunction "95_P$95") (pintype "bidirectional"))
    )
    (net (code "32") (name "RS_LW_SOC_DEBUGM_TMS") (class "Default")
      (node (ref "ALL_JTAG") (pin "7") (pinfunction "7_7") (pintype "passive"))
      (node (ref "SOCKET") (pin "P$85") (pinfunction "85_P$85") (pintype "bidirectional"))
    )
    (net (code "33") (name "RS_LW_SOC_I0") (class "Default")
      (node (ref "GPIO_IN") (pin "8") (pinfunction "8_8") (pintype "passive"))
      (node (ref "SOCKET") (pin "P$27") (pinfunction "27_P$27") (pintype "bidirectional"))
    )
    (net (code "34") (name "RS_LW_SOC_I1") (class "Default")
      (node (ref "GPIO_IN") (pin "7") (pinfunction "7_7") (pintype "passive"))
      (node (ref "SOCKET") (pin "P$30") (pinfunction "30_P$30") (pintype "bidirectional"))
    )
    (net (code "35") (name "RS_LW_SOC_I2") (class "Default")
      (node (ref "GPIO_IN") (pin "6") (pinfunction "6_6") (pintype "passive"))
      (node (ref "SOCKET") (pin "P$32") (pinfunction "32_P$32") (pintype "bidirectional"))
    )
    (net (code "36") (name "RS_LW_SOC_I3") (class "Default")
      (node (ref "GPIO_IN") (pin "5") (pinfunction "5_5") (pintype "passive"))
      (node (ref "SOCKET") (pin "P$34") (pinfunction "34_P$34") (pintype "bidirectional"))
    )
    (net (code "37") (name "RS_LW_SOC_I4") (class "Default")
      (node (ref "GPIO_IN") (pin "4") (pinfunction "4_4") (pintype "passive"))
      (node (ref "SOCKET") (pin "P$37") (pinfunction "37_P$37") (pintype "bidirectional"))
    )
    (net (code "38") (name "RS_LW_SOC_I5") (class "Default")
      (node (ref "GPIO_IN") (pin "3") (pinfunction "3_3") (pintype "passive"))
      (node (ref "SOCKET") (pin "P$39") (pinfunction "39_P$39") (pintype "bidirectional"))
    )
    (net (code "39") (name "RS_LW_SOC_I6") (class "Default")
      (node (ref "GPIO_IN") (pin "2") (pinfunction "2_2") (pintype "passive"))
      (node (ref "SOCKET") (pin "P$48") (pinfunction "48_P$48") (pintype "bidirectional"))
    )
    (net (code "40") (name "RS_LW_SOC_I7") (class "Default")
      (node (ref "GPIO_IN") (pin "1") (pinfunction "1_1") (pintype "passive"))
      (node (ref "SOCKET") (pin "P$50") (pinfunction "50_P$50") (pintype "bidirectional"))
    )
    (net (code "41") (name "RS_LW_SOC_I8") (class "Default")
      (node (ref "RS_UART") (pin "2") (pinfunction "2_2") (pintype "passive"))
      (node (ref "SOCKET") (pin "P$53") (pinfunction "53_P$53") (pintype "bidirectional"))
    )
    (net (code "42") (name "RS_LW_SOC_O0") (class "Default")
      (node (ref "GPIO_OUT") (pin "8") (pinfunction "8_8") (pintype "passive"))
      (node (ref "LW_O0") (pin "A") (pinfunction "A_A") (pintype "passive"))
      (node (ref "SOCKET") (pin "P$57") (pinfunction "57_P$57") (pintype "bidirectional"))
    )
    (net (code "43") (name "RS_LW_SOC_O1") (class "Default")
      (node (ref "GPIO_OUT") (pin "7") (pinfunction "7_7") (pintype "passive"))
      (node (ref "LW_O1") (pin "A") (pinfunction "A_A") (pintype "passive"))
      (node (ref "SOCKET") (pin "P$59") (pinfunction "59_P$59") (pintype "bidirectional"))
    )
    (net (code "44") (name "RS_LW_SOC_O2") (class "Default")
      (node (ref "GPIO_OUT") (pin "6") (pinfunction "6_6") (pintype "passive"))
      (node (ref "SOCKET") (pin "P$61") (pinfunction "61_P$61") (pintype "bidirectional"))
    )
    (net (code "45") (name "RS_LW_SOC_O3") (class "Default")
      (node (ref "GPIO_OUT") (pin "5") (pinfunction "5_5") (pintype "passive"))
      (node (ref "SOCKET") (pin "P$63") (pinfunction "63_P$63") (pintype "bidirectional"))
    )
    (net (code "46") (name "RS_LW_SOC_O4") (class "Default")
      (node (ref "GPIO_OUT") (pin "4") (pinfunction "4_4") (pintype "passive"))
      (node (ref "SOCKET") (pin "P$65") (pinfunction "65_P$65") (pintype "bidirectional"))
    )
    (net (code "47") (name "RS_LW_SOC_O5") (class "Default")
      (node (ref "GPIO_OUT") (pin "3") (pinfunction "3_3") (pintype "passive"))
      (node (ref "SOCKET") (pin "P$67") (pinfunction "67_P$67") (pintype "bidirectional"))
    )
    (net (code "48") (name "RS_LW_SOC_O6") (class "Default")
      (node (ref "GPIO_OUT") (pin "2") (pinfunction "2_2") (pintype "passive"))
      (node (ref "SOCKET") (pin "P$70") (pinfunction "70_P$70") (pintype "bidirectional"))
    )
    (net (code "49") (name "RS_LW_SOC_O7") (class "Default")
      (node (ref "GPIO_OUT") (pin "1") (pinfunction "1_1") (pintype "passive"))
      (node (ref "SOCKET") (pin "P$72") (pinfunction "72_P$72") (pintype "bidirectional"))
    )
    (net (code "50") (name "RS_LW_SOC_O8") (class "Default")
      (node (ref "RS_UART") (pin "4") (pinfunction "4_4") (pintype "passive"))
      (node (ref "SOCKET") (pin "P$81") (pinfunction "81_P$81") (pintype "bidirectional"))
    )
    (net (code "51") (name "RS_LW_SOC_QSPI_CLK") (class "Default")
      (node (ref "RS_FLASH") (pin "6") (pinfunction "6_6") (pintype "passive"))
      (node (ref "SOCKET") (pin "P$20") (pinfunction "20_P$20") (pintype "bidirectional"))
    )
    (net (code "52") (name "RS_LW_SOC_QSPI_MISO") (class "Default")
      (node (ref "RS_FLASH") (pin "8") (pinfunction "8_8") (pintype "passive"))
      (node (ref "SOCKET") (pin "P$24") (pinfunction "24_P$24") (pintype "bidirectional"))
    )
    (net (code "53") (name "RS_LW_SOC_QSPI_MOSI") (class "Default")
      (node (ref "RS_FLASH") (pin "10") (pinfunction "10_10") (pintype "passive"))
      (node (ref "SOCKET") (pin "P$22") (pinfunction "22_P$22") (pintype "bidirectional"))
    )
    (net (code "54") (name "RS_LW_SOC_QSPI_SS") (class "Default")
      (node (ref "RS_FLASH") (pin "12") (pinfunction "12_12") (pintype "passive"))
      (node (ref "SOCKET") (pin "P$18") (pinfunction "18_P$18") (pintype "bidirectional"))
    )
    (net (code "55") (name "RS_LW_SOC_RST") (class "Default")
      (node (ref "RS_RST") (pin "1") (pinfunction "1_1") (pintype "passive"))
      (node (ref "SOCKET") (pin "P$15") (pinfunction "15_P$15") (pintype "bidirectional"))
    )
    (net (code "56") (name "RS_LW_SOC_VDD") (class "Default")
      (node (ref "BOTTOM_VDD") (pin "5") (pinfunction "5_5") (pintype "passive"))
      (node (ref "C30") (pin "1") (pinfunction "1_1") (pintype "passive"))
      (node (ref "C31") (pin "1") (pinfunction "1_1") (pintype "passive"))
      (node (ref "SOCKET") (pin "P$13") (pinfunction "13_P$13") (pintype "bidirectional"))
    )
    (net (code "57") (name "RS_PHOTON_BEETLE_VDD") (class "Default")
      (node (ref "C40") (pin "1") (pinfunction "1_1") (pintype "passive"))
      (node (ref "C41") (pin "1") (pinfunction "1_1") (pintype "passive"))
      (node (ref "SOCKET") (pin "P$97") (pinfunction "97_P$97") (pintype "bidirectional"))
      (node (ref "TOP_VDD") (pin "7") (pinfunction "7_7") (pintype "passive"))
    )
    (net (code "58") (name "RS_ROMULUS_VDD") (class "Default")
      (node (ref "C38") (pin "1") (pinfunction "1_1") (pintype "passive"))
      (node (ref "C39") (pin "1") (pinfunction "1_1") (pintype "passive"))
      (node (ref "SOCKET") (pin "P$101") (pinfunction "101_P$101") (pintype "bidirectional"))
      (node (ref "TOP_VDD") (pin "5") (pinfunction "5_5") (pintype "passive"))
    )
    (net (code "59") (name "RS_SPARKLE_VDD") (class "Default")
      (node (ref "C46") (pin "1") (pinfunction "1_1") (pintype "passive"))
      (node (ref "C47") (pin "1") (pinfunction "1_1") (pintype "passive"))
      (node (ref "SOCKET") (pin "P$111") (pinfunction "111_P$111") (pintype "bidirectional"))
      (node (ref "TOP_VDD") (pin "3") (pinfunction "3_3") (pintype "passive"))
    )
    (net (code "60") (name "RS_TINYJAMBU_VDD") (class "Default")
      (node (ref "C44") (pin "1") (pinfunction "1_1") (pintype "passive"))
      (node (ref "C45") (pin "1") (pinfunction "1_1") (pintype "passive"))
      (node (ref "SOCKET") (pin "P$115") (pinfunction "115_P$115") (pintype "bidirectional"))
      (node (ref "TOP_VDD") (pin "1") (pinfunction "1_1") (pintype "passive"))
    )
    (net (code "61") (name "RS_TRNG_VDD") (class "Default")
      (node (ref "C50") (pin "1") (pinfunction "1_1") (pintype "passive"))
      (node (ref "C51") (pin "1") (pinfunction "1_1") (pintype "passive"))
      (node (ref "LEFT_VDD") (pin "3") (pinfunction "3_3") (pintype "passive"))
      (node (ref "SOCKET") (pin "P$143") (pinfunction "143_P$143") (pintype "bidirectional"))
    )
    (net (code "62") (name "RS_VBN") (class "Default")
      (node (ref "BIAS") (pin "3") (pinfunction "3_3") (pintype "passive"))
      (node (ref "C16") (pin "1") (pinfunction "1_1") (pintype "passive"))
      (node (ref "C17") (pin "1") (pinfunction "1_1") (pintype "passive"))
      (node (ref "SOCKET") (pin "P$141") (pinfunction "141_P$141") (pintype "bidirectional"))
    )
    (net (code "63") (name "RS_VBP") (class "Default")
      (node (ref "BIAS") (pin "1") (pinfunction "1_1") (pintype "passive"))
      (node (ref "C14") (pin "1") (pinfunction "1_1") (pintype "passive"))
      (node (ref "C15") (pin "1") (pinfunction "1_1") (pintype "passive"))
      (node (ref "SOCKET") (pin "P$145") (pinfunction "145_P$145") (pintype "bidirectional"))
    )
    (net (code "64") (name "RS_XOODYAK_VDD") (class "Default")
      (node (ref "C52") (pin "1") (pinfunction "1_1") (pintype "passive"))
      (node (ref "C53") (pin "1") (pinfunction "1_1") (pintype "passive"))
      (node (ref "LEFT_VDD") (pin "5") (pinfunction "5_5") (pintype "passive"))
      (node (ref "SOCKET") (pin "P$139") (pinfunction "139_P$139") (pintype "bidirectional"))
    )
    (net (code "65") (name "VCCQ") (class "Default")
      (node (ref "C18") (pin "1") (pinfunction "1_1") (pintype "passive"))
      (node (ref "C19") (pin "1") (pinfunction "1_1") (pintype "passive"))
      (node (ref "CHIP") (pin "3") (pinfunction "3_3") (pintype "passive"))
      (node (ref "SOCKET") (pin "P$19") (pinfunction "19_P$19") (pintype "bidirectional"))
      (node (ref "SOCKET") (pin "P$3") (pinfunction "3_P$3") (pintype "bidirectional"))
      (node (ref "SOCKET") (pin "P$33") (pinfunction "33_P$33") (pintype "bidirectional"))
      (node (ref "SOCKET") (pin "P$55") (pinfunction "55_P$55") (pintype "bidirectional"))
      (node (ref "SOCKET") (pin "P$69") (pinfunction "69_P$69") (pintype "bidirectional"))
      (node (ref "SOCKET") (pin "P$88") (pinfunction "88_P$88") (pintype "bidirectional"))
    )
    (net (code "66") (name "VDDA") (class "Default")
      (node (ref "SOCKET") (pin "P$130") (pinfunction "130_P$130") (pintype "bidirectional"))
    )
    (net (code "67") (name "VDDH") (class "Default")
      (node (ref "C20") (pin "1") (pinfunction "1_1") (pintype "passive"))
      (node (ref "C21") (pin "1") (pinfunction "1_1") (pintype "passive"))
      (node (ref "CHIP") (pin "5") (pinfunction "5_5") (pintype "passive"))
      (node (ref "SOCKET") (pin "P$103") (pinfunction "103_P$103") (pintype "bidirectional"))
    )
    (net (code "68") (name "VDDLS") (class "Default")
      (node (ref "C22") (pin "1") (pinfunction "1_1") (pintype "passive"))
      (node (ref "C23") (pin "1") (pinfunction "1_1") (pintype "passive"))
      (node (ref "CHIP") (pin "7") (pinfunction "7_7") (pintype "passive"))
      (node (ref "SOCKET") (pin "P$8") (pinfunction "8_P$8") (pintype "bidirectional"))
    )
    (net (code "69") (name "VDD_3.3V") (class "Default")
      (node (ref "ALL_JTAG") (pin "1") (pinfunction "1_1") (pintype "passive"))
      (node (ref "ALL_JTAG") (pin "2") (pinfunction "2_2") (pintype "passive"))
      (node (ref "C54") (pin "1") (pinfunction "1_1") (pintype "passive"))
      (node (ref "CHIP") (pin "1") (pinfunction "1_1") (pintype "passive"))
      (node (ref "IC4") (pin "5") (pinfunction "VCC_5") (pintype "bidirectional"))
      (node (ref "IC5") (pin "5") (pinfunction "VCC_5") (pintype "power_in"))
      (node (ref "R9") (pin "2") (pinfunction "2_2") (pintype "passive"))
      (node (ref "RS_FLASH") (pin "1") (pinfunction "1_1") (pintype "passive"))
      (node (ref "RS_FLASH") (pin "2") (pinfunction "2_2") (pintype "passive"))
      (node (ref "RS_UART") (pin "3") (pinfunction "3_3") (pintype "passive"))
      (node (ref "S4") (pin "1") (pinfunction "ON_1_1") (pintype "bidirectional"))
    )
    (net (code "70") (name "VDD_5V_UART") (class "Default")
      (node (ref "POWER_IN") (pin "2") (pinfunction "2_2") (pintype "passive"))
      (node (ref "USB-UART_4") (pin "2") (pinfunction "2_2") (pintype "passive"))
    )
    (net (code "71") (name "unconnected-(ALL_JTAG-Pad11)") (class "Default")
      (node (ref "ALL_JTAG") (pin "11") (pinfunction "11_11") (pintype "passive"))
    )
    (net (code "72") (name "unconnected-(ALL_JTAG-Pad15)") (class "Default")
      (node (ref "ALL_JTAG") (pin "15") (pinfunction "15_15") (pintype "passive"))
    )
    (net (code "73") (name "unconnected-(ALL_JTAG-Pad17)") (class "Default")
      (node (ref "ALL_JTAG") (pin "17") (pinfunction "17_17") (pintype "passive"))
    )
    (net (code "74") (name "unconnected-(ALL_JTAG-Pad19)") (class "Default")
      (node (ref "ALL_JTAG") (pin "19") (pinfunction "19_19") (pintype "passive"))
    )
    (net (code "75") (name "unconnected-(IC1-N{slash}C-Pad4)") (class "Default")
      (node (ref "IC1") (pin "4") (pinfunction "N/C_4") (pintype "no_connect"))
    )
    (net (code "76") (name "unconnected-(IC2-N{slash}C-Pad4)") (class "Default")
      (node (ref "IC2") (pin "4") (pinfunction "N/C_4") (pintype "no_connect"))
    )
    (net (code "77") (name "unconnected-(IC3-N{slash}C-Pad4)") (class "Default")
      (node (ref "IC3") (pin "4") (pinfunction "N/C_4") (pintype "no_connect"))
    )
    (net (code "78") (name "unconnected-(IC4-N.C..-Pad1)") (class "Default")
      (node (ref "IC4") (pin "1") (pinfunction "N.C.._1") (pintype "bidirectional"))
    )
    (net (code "79") (name "unconnected-(IC5-NC-Pad1)") (class "Default")
      (node (ref "IC5") (pin "1") (pinfunction "NC_1") (pintype "no_connect"))
    )
    (net (code "80") (name "unconnected-(RS_FLASH-Pad5)") (class "Default")
      (node (ref "RS_FLASH") (pin "5") (pinfunction "5_5") (pintype "passive"))
    )
    (net (code "81") (name "unconnected-(RS_FLASH-Pad7)") (class "Default")
      (node (ref "RS_FLASH") (pin "7") (pinfunction "7_7") (pintype "passive"))
    )
    (net (code "82") (name "unconnected-(RS_FLASH-Pad9)") (class "Default")
      (node (ref "RS_FLASH") (pin "9") (pinfunction "9_9") (pintype "passive"))
    )
    (net (code "83") (name "unconnected-(RS_FLASH-Pad11)") (class "Default")
      (node (ref "RS_FLASH") (pin "11") (pinfunction "11_11") (pintype "passive"))
    )
    (net (code "84") (name "unconnected-(SOCKET-1-PadP$1)") (class "Default")
      (node (ref "SOCKET") (pin "P$1") (pinfunction "1_P$1") (pintype "bidirectional"))
    )
    (net (code "85") (name "unconnected-(SOCKET-2-PadP$2)") (class "Default")
      (node (ref "SOCKET") (pin "P$2") (pinfunction "2_P$2") (pintype "bidirectional"))
    )
    (net (code "86") (name "unconnected-(SOCKET-4-PadP$4)") (class "Default")
      (node (ref "SOCKET") (pin "P$4") (pinfunction "4_P$4") (pintype "bidirectional"))
    )
    (net (code "87") (name "unconnected-(SOCKET-5-PadP$5)") (class "Default")
      (node (ref "SOCKET") (pin "P$5") (pinfunction "5_P$5") (pintype "bidirectional"))
    )
    (net (code "88") (name "unconnected-(SOCKET-7-PadP$7)") (class "Default")
      (node (ref "SOCKET") (pin "P$7") (pinfunction "7_P$7") (pintype "bidirectional"))
    )
    (net (code "89") (name "unconnected-(SOCKET-9-PadP$9)") (class "Default")
      (node (ref "SOCKET") (pin "P$9") (pinfunction "9_P$9") (pintype "bidirectional"))
    )
    (net (code "90") (name "unconnected-(SOCKET-12-PadP$12)") (class "Default")
      (node (ref "SOCKET") (pin "P$12") (pinfunction "12_P$12") (pintype "bidirectional"))
    )
    (net (code "91") (name "unconnected-(SOCKET-14-PadP$14)") (class "Default")
      (node (ref "SOCKET") (pin "P$14") (pinfunction "14_P$14") (pintype "bidirectional"))
    )
    (net (code "92") (name "unconnected-(SOCKET-16-PadP$16)") (class "Default")
      (node (ref "SOCKET") (pin "P$16") (pinfunction "16_P$16") (pintype "bidirectional"))
    )
    (net (code "93") (name "unconnected-(SOCKET-26-PadP$26)") (class "Default")
      (node (ref "SOCKET") (pin "P$26") (pinfunction "26_P$26") (pintype "bidirectional"))
    )
    (net (code "94") (name "unconnected-(SOCKET-28-PadP$28)") (class "Default")
      (node (ref "SOCKET") (pin "P$28") (pinfunction "28_P$28") (pintype "bidirectional"))
    )
    (net (code "95") (name "unconnected-(SOCKET-36-PadP$36)") (class "Default")
      (node (ref "SOCKET") (pin "P$36") (pinfunction "36_P$36") (pintype "bidirectional"))
    )
    (net (code "96") (name "unconnected-(SOCKET-38-PadP$38)") (class "Default")
      (node (ref "SOCKET") (pin "P$38") (pinfunction "38_P$38") (pintype "bidirectional"))
    )
    (net (code "97") (name "unconnected-(SOCKET-40-PadP$40)") (class "Default")
      (node (ref "SOCKET") (pin "P$40") (pinfunction "40_P$40") (pintype "bidirectional"))
    )
    (net (code "98") (name "unconnected-(SOCKET-41-PadP$41)") (class "Default")
      (node (ref "SOCKET") (pin "P$41") (pinfunction "41_P$41") (pintype "bidirectional"))
    )
    (net (code "99") (name "unconnected-(SOCKET-42-PadP$42)") (class "Default")
      (node (ref "SOCKET") (pin "P$42") (pinfunction "42_P$42") (pintype "bidirectional"))
    )
    (net (code "100") (name "unconnected-(SOCKET-43-PadP$43)") (class "Default")
      (node (ref "SOCKET") (pin "P$43") (pinfunction "43_P$43") (pintype "bidirectional"))
    )
    (net (code "101") (name "unconnected-(SOCKET-44-PadP$44)") (class "Default")
      (node (ref "SOCKET") (pin "P$44") (pinfunction "44_P$44") (pintype "bidirectional"))
    )
    (net (code "102") (name "unconnected-(SOCKET-45-PadP$45)") (class "Default")
      (node (ref "SOCKET") (pin "P$45") (pinfunction "45_P$45") (pintype "bidirectional"))
    )
    (net (code "103") (name "unconnected-(SOCKET-46-PadP$46)") (class "Default")
      (node (ref "SOCKET") (pin "P$46") (pinfunction "46_P$46") (pintype "bidirectional"))
    )
    (net (code "104") (name "unconnected-(SOCKET-47-PadP$47)") (class "Default")
      (node (ref "SOCKET") (pin "P$47") (pinfunction "47_P$47") (pintype "bidirectional"))
    )
    (net (code "105") (name "unconnected-(SOCKET-52-PadP$52)") (class "Default")
      (node (ref "SOCKET") (pin "P$52") (pinfunction "52_P$52") (pintype "bidirectional"))
    )
    (net (code "106") (name "unconnected-(SOCKET-54-PadP$54)") (class "Default")
      (node (ref "SOCKET") (pin "P$54") (pinfunction "54_P$54") (pintype "bidirectional"))
    )
    (net (code "107") (name "unconnected-(SOCKET-56-PadP$56)") (class "Default")
      (node (ref "SOCKET") (pin "P$56") (pinfunction "56_P$56") (pintype "bidirectional"))
    )
    (net (code "108") (name "unconnected-(SOCKET-66-PadP$66)") (class "Default")
      (node (ref "SOCKET") (pin "P$66") (pinfunction "66_P$66") (pintype "bidirectional"))
    )
    (net (code "109") (name "unconnected-(SOCKET-68-PadP$68)") (class "Default")
      (node (ref "SOCKET") (pin "P$68") (pinfunction "68_P$68") (pintype "bidirectional"))
    )
    (net (code "110") (name "unconnected-(SOCKET-73-PadP$73)") (class "Default")
      (node (ref "SOCKET") (pin "P$73") (pinfunction "73_P$73") (pintype "bidirectional"))
    )
    (net (code "111") (name "unconnected-(SOCKET-74-PadP$74)") (class "Default")
      (node (ref "SOCKET") (pin "P$74") (pinfunction "74_P$74") (pintype "bidirectional"))
    )
    (net (code "112") (name "unconnected-(SOCKET-75-PadP$75)") (class "Default")
      (node (ref "SOCKET") (pin "P$75") (pinfunction "75_P$75") (pintype "bidirectional"))
    )
    (net (code "113") (name "unconnected-(SOCKET-76-PadP$76)") (class "Default")
      (node (ref "SOCKET") (pin "P$76") (pinfunction "76_P$76") (pintype "bidirectional"))
    )
    (net (code "114") (name "unconnected-(SOCKET-77-PadP$77)") (class "Default")
      (node (ref "SOCKET") (pin "P$77") (pinfunction "77_P$77") (pintype "bidirectional"))
    )
    (net (code "115") (name "unconnected-(SOCKET-78-PadP$78)") (class "Default")
      (node (ref "SOCKET") (pin "P$78") (pinfunction "78_P$78") (pintype "bidirectional"))
    )
    (net (code "116") (name "unconnected-(SOCKET-79-PadP$79)") (class "Default")
      (node (ref "SOCKET") (pin "P$79") (pinfunction "79_P$79") (pintype "bidirectional"))
    )
    (net (code "117") (name "unconnected-(SOCKET-80-PadP$80)") (class "Default")
      (node (ref "SOCKET") (pin "P$80") (pinfunction "80_P$80") (pintype "bidirectional"))
    )
    (net (code "118") (name "unconnected-(SOCKET-82-PadP$82)") (class "Default")
      (node (ref "SOCKET") (pin "P$82") (pinfunction "82_P$82") (pintype "bidirectional"))
    )
    (net (code "119") (name "unconnected-(SOCKET-84-PadP$84)") (class "Default")
      (node (ref "SOCKET") (pin "P$84") (pinfunction "84_P$84") (pintype "bidirectional"))
    )
    (net (code "120") (name "unconnected-(SOCKET-89-PadP$89)") (class "Default")
      (node (ref "SOCKET") (pin "P$89") (pinfunction "89_P$89") (pintype "bidirectional"))
    )
    (net (code "121") (name "unconnected-(SOCKET-92-PadP$92)") (class "Default")
      (node (ref "SOCKET") (pin "P$92") (pinfunction "92_P$92") (pintype "bidirectional"))
    )
    (net (code "122") (name "unconnected-(SOCKET-94-PadP$94)") (class "Default")
      (node (ref "SOCKET") (pin "P$94") (pinfunction "94_P$94") (pintype "bidirectional"))
    )
    (net (code "123") (name "unconnected-(SOCKET-96-PadP$96)") (class "Default")
      (node (ref "SOCKET") (pin "P$96") (pinfunction "96_P$96") (pintype "bidirectional"))
    )
    (net (code "124") (name "unconnected-(SOCKET-100-PadP$100)") (class "Default")
      (node (ref "SOCKET") (pin "P$100") (pinfunction "100_P$100") (pintype "bidirectional"))
    )
    (net (code "125") (name "unconnected-(SOCKET-102-PadP$102)") (class "Default")
      (node (ref "SOCKET") (pin "P$102") (pinfunction "102_P$102") (pintype "bidirectional"))
    )
    (net (code "126") (name "unconnected-(SOCKET-104-PadP$104)") (class "Default")
      (node (ref "SOCKET") (pin "P$104") (pinfunction "104_P$104") (pintype "bidirectional"))
    )
    (net (code "127") (name "unconnected-(SOCKET-106-PadP$106)") (class "Default")
      (node (ref "SOCKET") (pin "P$106") (pinfunction "106_P$106") (pintype "bidirectional"))
    )
    (net (code "128") (name "unconnected-(SOCKET-107-PadP$107)") (class "Default")
      (node (ref "SOCKET") (pin "P$107") (pinfunction "107_P$107") (pintype "bidirectional"))
    )
    (net (code "129") (name "unconnected-(SOCKET-108-PadP$108)") (class "Default")
      (node (ref "SOCKET") (pin "P$108") (pinfunction "108_P$108") (pintype "bidirectional"))
    )
    (net (code "130") (name "unconnected-(SOCKET-110-PadP$110)") (class "Default")
      (node (ref "SOCKET") (pin "P$110") (pinfunction "110_P$110") (pintype "bidirectional"))
    )
    (net (code "131") (name "unconnected-(SOCKET-112-PadP$112)") (class "Default")
      (node (ref "SOCKET") (pin "P$112") (pinfunction "112_P$112") (pintype "bidirectional"))
    )
    (net (code "132") (name "unconnected-(SOCKET-114-PadP$114)") (class "Default")
      (node (ref "SOCKET") (pin "P$114") (pinfunction "114_P$114") (pintype "bidirectional"))
    )
    (net (code "133") (name "unconnected-(SOCKET-116-PadP$116)") (class "Default")
      (node (ref "SOCKET") (pin "P$116") (pinfunction "116_P$116") (pintype "bidirectional"))
    )
    (net (code "134") (name "unconnected-(SOCKET-117-PadP$117)") (class "Default")
      (node (ref "SOCKET") (pin "P$117") (pinfunction "117_P$117") (pintype "bidirectional"))
    )
    (net (code "135") (name "unconnected-(SOCKET-118-PadP$118)") (class "Default")
      (node (ref "SOCKET") (pin "P$118") (pinfunction "118_P$118") (pintype "bidirectional"))
    )
    (net (code "136") (name "unconnected-(SOCKET-119-PadP$119)") (class "Default")
      (node (ref "SOCKET") (pin "P$119") (pinfunction "119_P$119") (pintype "bidirectional"))
    )
    (net (code "137") (name "unconnected-(SOCKET-120-PadP$120)") (class "Default")
      (node (ref "SOCKET") (pin "P$120") (pinfunction "120_P$120") (pintype "bidirectional"))
    )
    (net (code "138") (name "unconnected-(SOCKET-121-PadP$121)") (class "Default")
      (node (ref "SOCKET") (pin "P$121") (pinfunction "121_P$121") (pintype "bidirectional"))
    )
    (net (code "139") (name "unconnected-(SOCKET-122-PadP$122)") (class "Default")
      (node (ref "SOCKET") (pin "P$122") (pinfunction "122_P$122") (pintype "bidirectional"))
    )
    (net (code "140") (name "unconnected-(SOCKET-123-PadP$123)") (class "Default")
      (node (ref "SOCKET") (pin "P$123") (pinfunction "123_P$123") (pintype "bidirectional"))
    )
    (net (code "141") (name "unconnected-(SOCKET-124-PadP$124)") (class "Default")
      (node (ref "SOCKET") (pin "P$124") (pinfunction "124_P$124") (pintype "bidirectional"))
    )
    (net (code "142") (name "unconnected-(SOCKET-125-PadP$125)") (class "Default")
      (node (ref "SOCKET") (pin "P$125") (pinfunction "125_P$125") (pintype "bidirectional"))
    )
    (net (code "143") (name "unconnected-(SOCKET-126-PadP$126)") (class "Default")
      (node (ref "SOCKET") (pin "P$126") (pinfunction "126_P$126") (pintype "bidirectional"))
    )
    (net (code "144") (name "unconnected-(SOCKET-127-PadP$127)") (class "Default")
      (node (ref "SOCKET") (pin "P$127") (pinfunction "127_P$127") (pintype "bidirectional"))
    )
    (net (code "145") (name "unconnected-(SOCKET-128-PadP$128)") (class "Default")
      (node (ref "SOCKET") (pin "P$128") (pinfunction "128_P$128") (pintype "bidirectional"))
    )
    (net (code "146") (name "unconnected-(SOCKET-129-PadP$129)") (class "Default")
      (node (ref "SOCKET") (pin "P$129") (pinfunction "129_P$129") (pintype "bidirectional"))
    )
    (net (code "147") (name "unconnected-(SOCKET-131-PadP$131)") (class "Default")
      (node (ref "SOCKET") (pin "P$131") (pinfunction "131_P$131") (pintype "bidirectional"))
    )
    (net (code "148") (name "unconnected-(SOCKET-132-PadP$132)") (class "Default")
      (node (ref "SOCKET") (pin "P$132") (pinfunction "132_P$132") (pintype "bidirectional"))
    )
    (net (code "149") (name "unconnected-(SOCKET-134-PadP$134)") (class "Default")
      (node (ref "SOCKET") (pin "P$134") (pinfunction "134_P$134") (pintype "bidirectional"))
    )
    (net (code "150") (name "unconnected-(SOCKET-135-PadP$135)") (class "Default")
      (node (ref "SOCKET") (pin "P$135") (pinfunction "135_P$135") (pintype "bidirectional"))
    )
    (net (code "151") (name "unconnected-(SOCKET-136-PadP$136)") (class "Default")
      (node (ref "SOCKET") (pin "P$136") (pinfunction "136_P$136") (pintype "bidirectional"))
    )
    (net (code "152") (name "unconnected-(SOCKET-138-PadP$138)") (class "Default")
      (node (ref "SOCKET") (pin "P$138") (pinfunction "138_P$138") (pintype "bidirectional"))
    )
    (net (code "153") (name "unconnected-(SOCKET-140-PadP$140)") (class "Default")
      (node (ref "SOCKET") (pin "P$140") (pinfunction "140_P$140") (pintype "bidirectional"))
    )
    (net (code "154") (name "unconnected-(SOCKET-142-PadP$142)") (class "Default")
      (node (ref "SOCKET") (pin "P$142") (pinfunction "142_P$142") (pintype "bidirectional"))
    )
    (net (code "155") (name "unconnected-(SOCKET-144-PadP$144)") (class "Default")
      (node (ref "SOCKET") (pin "P$144") (pinfunction "144_P$144") (pintype "bidirectional"))
    )
    (net (code "156") (name "unconnected-(SOCKET-146-PadP$146)") (class "Default")
      (node (ref "SOCKET") (pin "P$146") (pinfunction "146_P$146") (pintype "bidirectional"))
    )
    (net (code "157") (name "unconnected-(SOCKET-147-PadP$147)") (class "Default")
      (node (ref "SOCKET") (pin "P$147") (pinfunction "147_P$147") (pintype "bidirectional"))
    )
    (net (code "158") (name "unconnected-(SOCKET-148-PadP$148)") (class "Default")
      (node (ref "SOCKET") (pin "P$148") (pinfunction "148_P$148") (pintype "bidirectional"))
    )
    (net (code "159") (name "unconnected-(SOCKET-150-PadP$150)") (class "Default")
      (node (ref "SOCKET") (pin "P$150") (pinfunction "150_P$150") (pintype "bidirectional"))
    )
    (net (code "160") (name "unconnected-(SOCKET-152-PadP$152)") (class "Default")
      (node (ref "SOCKET") (pin "P$152") (pinfunction "152_P$152") (pintype "bidirectional"))
    )
    (net (code "161") (name "unconnected-(SOCKET-153-PadP$153)") (class "Default")
      (node (ref "SOCKET") (pin "P$153") (pinfunction "153_P$153") (pintype "bidirectional"))
    )
    (net (code "162") (name "unconnected-(SOCKET-154-PadP$154)") (class "Default")
      (node (ref "SOCKET") (pin "P$154") (pinfunction "154_P$154") (pintype "bidirectional"))
    )
    (net (code "163") (name "unconnected-(SOCKET-155-PadP$155)") (class "Default")
      (node (ref "SOCKET") (pin "P$155") (pinfunction "155_P$155") (pintype "bidirectional"))
    )
    (net (code "164") (name "unconnected-(SOCKET-156-PadP$156)") (class "Default")
      (node (ref "SOCKET") (pin "P$156") (pinfunction "156_P$156") (pintype "bidirectional"))
    )
    (net (code "165") (name "unconnected-(SOCKET-157-PadP$157)") (class "Default")
      (node (ref "SOCKET") (pin "P$157") (pinfunction "157_P$157") (pintype "bidirectional"))
    )
    (net (code "166") (name "unconnected-(SOCKET-158-PadP$158)") (class "Default")
      (node (ref "SOCKET") (pin "P$158") (pinfunction "158_P$158") (pintype "bidirectional"))
    )
    (net (code "167") (name "unconnected-(SOCKET-159-PadP$159)") (class "Default")
      (node (ref "SOCKET") (pin "P$159") (pinfunction "159_P$159") (pintype "bidirectional"))
    )
    (net (code "168") (name "unconnected-(SOCKET-160-PadP$160)") (class "Default")
      (node (ref "SOCKET") (pin "P$160") (pinfunction "160_P$160") (pintype "bidirectional"))
    )
    (net (code "169") (name "unconnected-(USB-UART_4-Pad1)") (class "Default")
      (node (ref "USB-UART_4") (pin "1") (pinfunction "1_1") (pintype "passive"))
    )
    (net (code "170") (name "unconnected-(USB-UART_4-Pad3)") (class "Default")
      (node (ref "USB-UART_4") (pin "3") (pinfunction "3_3") (pintype "passive"))
    )
    (net (code "171") (name "unconnected-(USB-UART_4-Pad4)") (class "Default")
      (node (ref "USB-UART_4") (pin "4") (pinfunction "4_4") (pintype "passive"))
    )
  )
)
